# 50_pin_0_5mm_FPC.net
KiCad netlist of a schematic drawn in EAGLE
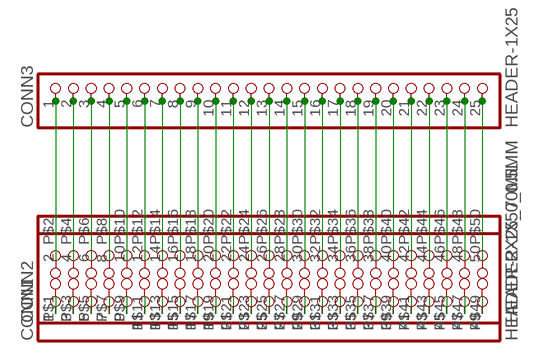
[diagram p0: schematic, sheet 1]

(export (version "E")
  (design (tool "Eeschema 10.0.6"))
  (components
    (comp (ref "CONN1")
      (value "HEADER-2X25_70MIL")
      (footprint "eagle-import:2X25")
      (libsource (lib "eagle-import") (part "HEADER-2X25_70MIL"))
    )
    (comp (ref "CONN2")
      (value "HEADER-1X50_0.5MM")
      (footprint "eagle-import:FPC_GENERIC_0.5MM_50PIN")
      (libsource (lib "eagle-import") (part "HEADER-1X50_0.5MM"))
    )
    (comp (ref "CONN3")
      (value "HEADER-1X25")
      (footprint "eagle-import:1X25_ROUND_70MIL")
      (libsource (lib "eagle-import") (part "HEADER-1X25"))
    )
  )
  (nets
    (net (code "1") (name "Net-(CONN2-1)") (class "Default")
      (node (ref "CONN1") (pin "1") (pinfunction "1_1") (pintype "passive"))
      (node (ref "CONN2") (pin "P$1") (pinfunction "1_P$1") (pintype "passive"))
    )
    (net (code "2") (name "Net-(CONN2-2)") (class "Default")
      (node (ref "CONN1") (pin "2") (pinfunction "2_2") (pintype "passive"))
      (node (ref "CONN2") (pin "P$2") (pinfunction "2_P$2") (pintype "passive"))
      (node (ref "CONN3") (pin "1") (pinfunction "1_1") (pintype "passive"))
    )
    (net (code "3") (name "Net-(CONN2-3)") (class "Default")
      (node (ref "CONN1") (pin "3") (pinfunction "3_3") (pintype "passive"))
      (node (ref "CONN2") (pin "P$3") (pinfunction "3_P$3") (pintype "passive"))
    )
    (net (code "4") (name "Net-(CONN2-4)") (class "Default")
      (node (ref "CONN1") (pin "4") (pinfunction "4_4") (pintype "passive"))
      (node (ref "CONN2") (pin "P$4") (pinfunction "4_P$4") (pintype "passive"))
      (node (ref "CONN3") (pin "2") (pinfunction "2_2") (pintype "passive"))
    )
    (net (code "5") (name "Net-(CONN2-5)") (class "Default")
      (node (ref "CONN1") (pin "5") (pinfunction "5_5") (pintype "passive"))
      (node (ref "CONN2") (pin "P$5") (pinfunction "5_P$5") (pintype "passive"))
    )
    (net (code "6") (name "Net-(CONN2-6)") (class "Default")
      (node (ref "CONN1") (pin "6") (pinfunction "6_6") (pintype "passive"))
      (node (ref "CONN2") (pin "P$6") (pinfunction "6_P$6") (pintype "passive"))
      (node (ref "CONN3") (pin "3") (pinfunction "3_3") (pintype "passive"))
    )
    (net (code "7") (name "Net-(CONN2-7)") (class "Default")
      (node (ref "CONN1") (pin "7") (pinfunction "7_7") (pintype "passive"))
      (node (ref "CONN2") (pin "P$7") (pinfunction "7_P$7") (pintype "passive"))
    )
    (net (code "8") (name "Net-(CONN2-8)") (class "Default")
      (node (ref "CONN1") (pin "8") (pinfunction "8_8") (pintype "passive"))
      (node (ref "CONN2") (pin "P$8") (pinfunction "8_P$8") (pintype "passive"))
      (node (ref "CONN3") (pin "4") (pinfunction "4_4") (pintype "passive"))
    )
    (net (code "9") (name "Net-(CONN2-9)") (class "Default")
      (node (ref "CONN1") (pin "9") (pinfunction "9_9") (pintype "passive"))
      (node (ref "CONN2") (pin "P$9") (pinfunction "9_P$9") (pintype "passive"))
    )
    (net (code "10") (name "Net-(CONN2-10)") (class "Default")
      (node (ref "CONN1") (pin "10") (pinfunction "10_10") (pintype "passive"))
      (node (ref "CONN2") (pin "P$10") (pinfunction "10_P$10") (pintype "passive"))
      (node (ref "CONN3") (pin "5") (pinfunction "5_5") (pintype "passive"))
    )
    (net (code "11") (name "Net-(CONN2-11)") (class "Default")
      (node (ref "CONN1") (pin "11") (pinfunction "11_11") (pintype "passive"))
      (node (ref "CONN2") (pin "P$11") (pinfunction "11_P$11") (pintype "passive"))
    )
    (net (code "12") (name "Net-(CONN2-12)") (class "Default")
      (node (ref "CONN1") (pin "12") (pinfunction "12_12") (pintype "passive"))
      (node (ref "CONN2") (pin "P$12") (pinfunction "12_P$12") (pintype "passive"))
      (node (ref "CONN3") (pin "6") (pinfunction "6_6") (pintype "passive"))
    )
    (net (code "13") (name "Net-(CONN2-13)") (class "Default")
      (node (ref "CONN1") (pin "13") (pinfunction "13_13") (pintype "passive"))
      (node (ref "CONN2") (pin "P$13") (pinfunction "13_P$13") (pintype "passive"))
    )
    (net (code "14") (name "Net-(CONN2-14)") (class "Default")
      (node (ref "CONN1") (pin "14") (pinfunction "14_14") (pintype "passive"))
      (node (ref "CONN2") (pin "P$14") (pinfunction "14_P$14") (pintype "passive"))
      (node (ref "CONN3") (pin "7") (pinfunction "7_7") (pintype "passive"))
    )
    (net (code "15") (name "Net-(CONN2-15)") (class "Default")
      (node (ref "CONN1") (pin "15") (pinfunction "15_15") (pintype "passive"))
      (node (ref "CONN2") (pin "P$15") (pinfunction "15_P$15") (pintype "passive"))
    )
    (net (code "16") (name "Net-(CONN2-16)") (class "Default")
      (node (ref "CONN1") (pin "16") (pinfunction "16_16") (pintype "passive"))
      (node (ref "CONN2") (pin "P$16") (pinfunction "16_P$16") (pintype "passive"))
      (node (ref "CONN3") (pin "8") (pinfunction "8_8") (pintype "passive"))
    )
    (net (code "17") (name "Net-(CONN2-17)") (class "Default")
      (node (ref "CONN1") (pin "17") (pinfunction "17_17") (pintype "passive"))
      (node (ref "CONN2") (pin "P$17") (pinfunction "17_P$17") (pintype "passive"))
    )
    (net (code "18") (name "Net-(CONN2-18)") (class "Default")
      (node (ref "CONN1") (pin "18") (pinfunction "18_18") (pintype "passive"))
      (node (ref "CONN2") (pin "P$18") (pinfunction "18_P$18") (pintype "passive"))
      (node (ref "CONN3") (pin "9") (pinfunction "9_9") (pintype "passive"))
    )
    (net (code "19") (name "Net-(CONN2-19)") (class "Default")
      (node (ref "CONN1") (pin "19") (pinfunction "19_19") (pintype "passive"))
      (node (ref "CONN2") (pin "P$19") (pinfunction "19_P$19") (pintype "passive"))
    )
    (net (code "20") (name "Net-(CONN2-20)") (class "Default")
      (node (ref "CONN1") (pin "20") (pinfunction "20_20") (pintype "passive"))
      (node (ref "CONN2") (pin "P$20") (pinfunction "20_P$20") (pintype "passive"))
      (node (ref "CONN3") (pin "10") (pinfunction "10_10") (pintype "passive"))
    )
    (net (code "21") (name "Net-(CONN2-21)") (class "Default")
      (node (ref "CONN1") (pin "21") (pinfunction "21_21") (pintype "passive"))
      (node (ref "CONN2") (pin "P$21") (pinfunction "21_P$21") (pintype "passive"))
    )
    (net (code "22") (name "Net-(CONN2-22)") (class "Default")
      (node (ref "CONN1") (pin "22") (pinfunction "22_22") (pintype "passive"))
      (node (ref "CONN2") (pin "P$22") (pinfunction "22_P$22") (pintype "passive"))
      (node (ref "CONN3") (pin "11") (pinfunction "11_11") (pintype "passive"))
    )
    (net (code "23") (name "Net-(CONN2-23)") (class "Default")
      (node (ref "CONN1") (pin "23") (pinfunction "23_23") (pintype "passive"))
      (node (ref "CONN2") (pin "P$23") (pinfunction "23_P$23") (pintype "passive"))
    )
    (net (code "24") (name "Net-(CONN2-24)") (class "Default")
      (node (ref "CONN1") (pin "24") (pinfunction "24_24") (pintype "passive"))
      (node (ref "CONN2") (pin "P$24") (pinfunction "24_P$24") (pintype "passive"))
      (node (ref "CONN3") (pin "12") (pinfunction "12_12") (pintype "passive"))
    )
    (net (code "25") (name "Net-(CONN2-25)") (class "Default")
      (node (ref "CONN1") (pin "25") (pinfunction "25_25") (pintype "passive"))
      (node (ref "CONN2") (pin "P$25") (pinfunction "25_P$25") (pintype "passive"))
    )
    (net (code "26") (name "Net-(CONN2-26)") (class "Default")
      (node (ref "CONN1") (pin "26") (pinfunction "26_26") (pintype "passive"))
      (node (ref "CONN2") (pin "P$26") (pinfunction "26_P$26") (pintype "passive"))
      (node (ref "CONN3") (pin "13") (pinfunction "13_13") (pintype "passive"))
    )
    (net (code "27") (name "Net-(CONN2-27)") (class "Default")
      (node (ref "CONN1") (pin "27") (pinfunction "27_27") (pintype "passive"))
      (node (ref "CONN2") (pin "P$27") (pinfunction "27_P$27") (pintype "passive"))
    )
    (net (code "28") (name "Net-(CONN2-28)") (class "Default")
      (node (ref "CONN1") (pin "28") (pinfunction "28_28") (pintype "passive"))
      (node (ref "CONN2") (pin "P$28") (pinfunction "28_P$28") (pintype "passive"))
      (node (ref "CONN3") (pin "14") (pinfunction "14_14") (pintype "passive"))
    )
    (net (code "29") (name "Net-(CONN2-29)") (class "Default")
      (node (ref "CONN1") (pin "29") (pinfunction "29_29") (pintype "passive"))
      (node (ref "CONN2") (pin "P$29") (pinfunction "29_P$29") (pintype "passive"))
    )
    (net (code "30") (name "Net-(CONN2-30)") (class "Default")
      (node (ref "CONN1") (pin "30") (pinfunction "30_30") (pintype "passive"))
      (node (ref "CONN2") (pin "P$30") (pinfunction "30_P$30") (pintype "passive"))
      (node (ref "CONN3") (pin "15") (pinfunction "15_15") (pintype "passive"))
    )
    (net (code "31") (name "Net-(CONN2-31)") (class "Default")
      (node (ref "CONN1") (pin "31") (pinfunction "31_31") (pintype "passive"))
      (node (ref "CONN2") (pin "P$31") (pinfunction "31_P$31") (pintype "passive"))
    )
    (net (code "32") (name "Net-(CONN2-32)") (class "Default")
      (node (ref "CONN1") (pin "32") (pinfunction "32_32") (pintype "passive"))
      (node (ref "CONN2") (pin "P$32") (pinfunction "32_P$32") (pintype "passive"))
      (node (ref "CONN3") (pin "16") (pinfunction "16_16") (pintype "passive"))
    )
    (net (code "33") (name "Net-(CONN2-33)") (class "Default")
      (node (ref "CONN1") (pin "33") (pinfunction "33_33") (pintype "passive"))
      (node (ref "CONN2") (pin "P$33") (pinfunction "33_P$33") (pintype "passive"))
    )
    (net (code "34") (name "Net-(CONN2-34)") (class "Default")
      (node (ref "CONN1") (pin "34") (pinfunction "34_34") (pintype "passive"))
      (node (ref "CONN2") (pin "P$34") (pinfunction "34_P$34") (pintype "passive"))
      (node (ref "CONN3") (pin "17") (pinfunction "17_17") (pintype "passive"))
    )
    (net (code "35") (name "Net-(CONN2-35)") (class "Default")
      (node (ref "CONN1") (pin "35") (pinfunction "35_35") (pintype "passive"))
      (node (ref "CONN2") (pin "P$35") (pinfunction "35_P$35") (pintype "passive"))
    )
    (net (code "36") (name "Net-(CONN2-36)") (class "Default")
      (node (ref "CONN1") (pin "36") (pinfunction "36_36") (pintype "passive"))
      (node (ref "CONN2") (pin "P$36") (pinfunction "36_P$36") (pintype "passive"))
      (node (ref "CONN3") (pin "18") (pinfunction "18_18") (pintype "passive"))
    )
    (net (code "37") (name "Net-(CONN2-37)") (class "Default")
      (node (ref "CONN1") (pin "37") (pinfunction "37_37") (pintype "passive"))
      (node (ref "CONN2") (pin "P$37") (pinfunction "37_P$37") (pintype "passive"))
    )
    (net (code "38") (name "Net-(CONN2-38)") (class "Default")
      (node (ref "CONN1") (pin "38") (pinfunction "38_38") (pintype "passive"))
      (node (ref "CONN2") (pin "P$38") (pinfunction "38_P$38") (pintype "passive"))
      (node (ref "CONN3") (pin "19") (pinfunction "19_19") (pintype "passive"))
    )
    (net (code "39") (name "Net-(CONN2-39)") (class "Default")
      (node (ref "CONN1") (pin "39") (pinfunction "39_39") (pintype "passive"))
      (node (ref "CONN2") (pin "P$39") (pinfunction "39_P$39") (pintype "passive"))
    )
    (net (code "40") (name "Net-(CONN2-40)") (class "Default")
      (node (ref "CONN1") (pin "40") (pinfunction "40_40") (pintype "passive"))
      (node (ref "CONN2") (pin "P$40") (pinfunction "40_P$40") (pintype "passive"))
      (node (ref "CONN3") (pin "20") (pinfunction "20_20") (pintype "passive"))
    )
    (net (code "41") (name "Net-(CONN2-41)") (class "Default")
      (node (ref "CONN1") (pin "41") (pinfunction "41_41") (pintype "passive"))
      (node (ref "CONN2") (pin "P$41") (pinfunction "41_P$41") (pintype "passive"))
    )
    (net (code "42") (name "Net-(CONN2-42)") (class "Default")
      (node (ref "CONN1") (pin "42") (pinfunction "42_42") (pintype "passive"))
      (node (ref "CONN2") (pin "P$42") (pinfunction "42_P$42") (pintype "passive"))
      (node (ref "CONN3") (pin "21") (pinfunction "21_21") (pintype "passive"))
    )
    (net (code "43") (name "Net-(CONN2-43)") (class "Default")
      (node (ref "CONN1") (pin "43") (pinfunction "43_43") (pintype "passive"))
      (node (ref "CONN2") (pin "P$43") (pinfunction "43_P$43") (pintype "passive"))
    )
    (net (code "44") (name "Net-(CONN2-44)") (class "Default")
      (node (ref "CONN1") (pin "44") (pinfunction "44_44") (pintype "passive"))
      (node (ref "CONN2") (pin "P$44") (pinfunction "44_P$44") (pintype "passive"))
      (node (ref "CONN3") (pin "22") (pinfunction "22_22") (pintype "passive"))
    )
    (net (code "45") (name "Net-(CONN2-45)") (class "Default")
      (node (ref "CONN1") (pin "45") (pinfunction "45_45") (pintype "passive"))
      (node (ref "CONN2") (pin "P$45") (pinfunction "45_P$45") (pintype "passive"))
    )
    (net (code "46") (name "Net-(CONN2-46)") (class "Default")
      (node (ref "CONN1") (pin "46") (pinfunction "46_46") (pintype "passive"))
      (node (ref "CONN2") (pin "P$46") (pinfunction "46_P$46") (pintype "passive"))
      (node (ref "CONN3") (pin "23") (pinfunction "23_23") (pintype "passive"))
    )
    (net (code "47") (name "Net-(CONN2-47)") (class "Default")
      (node (ref "CONN1") (pin "47") (pinfunction "47_47") (pintype "passive"))
      (node (ref "CONN2") (pin "P$47") (pinfunction "47_P$47") (pintype "passive"))
    )
    (net (code "48") (name "Net-(CONN2-48)") (class "Default")
      (node (ref "CONN1") (pin "48") (pinfunction "48_48") (pintype "passive"))
      (node (ref "CONN2") (pin "P$48") (pinfunction "48_P$48") (pintype "passive"))
      (node (ref "CONN3") (pin "24") (pinfunction "24_24") (pintype "passive"))
    )
    (net (code "49") (name "Net-(CONN2-49)") (class "Default")
      (node (ref "CONN1") (pin "49") (pinfunction "49_49") (pintype "passive"))
      (node (ref "CONN2") (pin "P$49") (pinfunction "49_P$49") (pintype "passive"))
    )
    (net (code "50") (name "Net-(CONN2-50)") (class "Default")
      (node (ref "CONN1") (pin "50") (pinfunction "50_50") (pintype "passive"))
      (node (ref "CONN2") (pin "P$50") (pinfunction "50_P$50") (pintype "passive"))
      (node (ref "CONN3") (pin "25") (pinfunction "25_25") (pintype "passive"))
    )
  )
)
